# AST1041.net
KiCad netlist of a schematic drawn in EAGLE
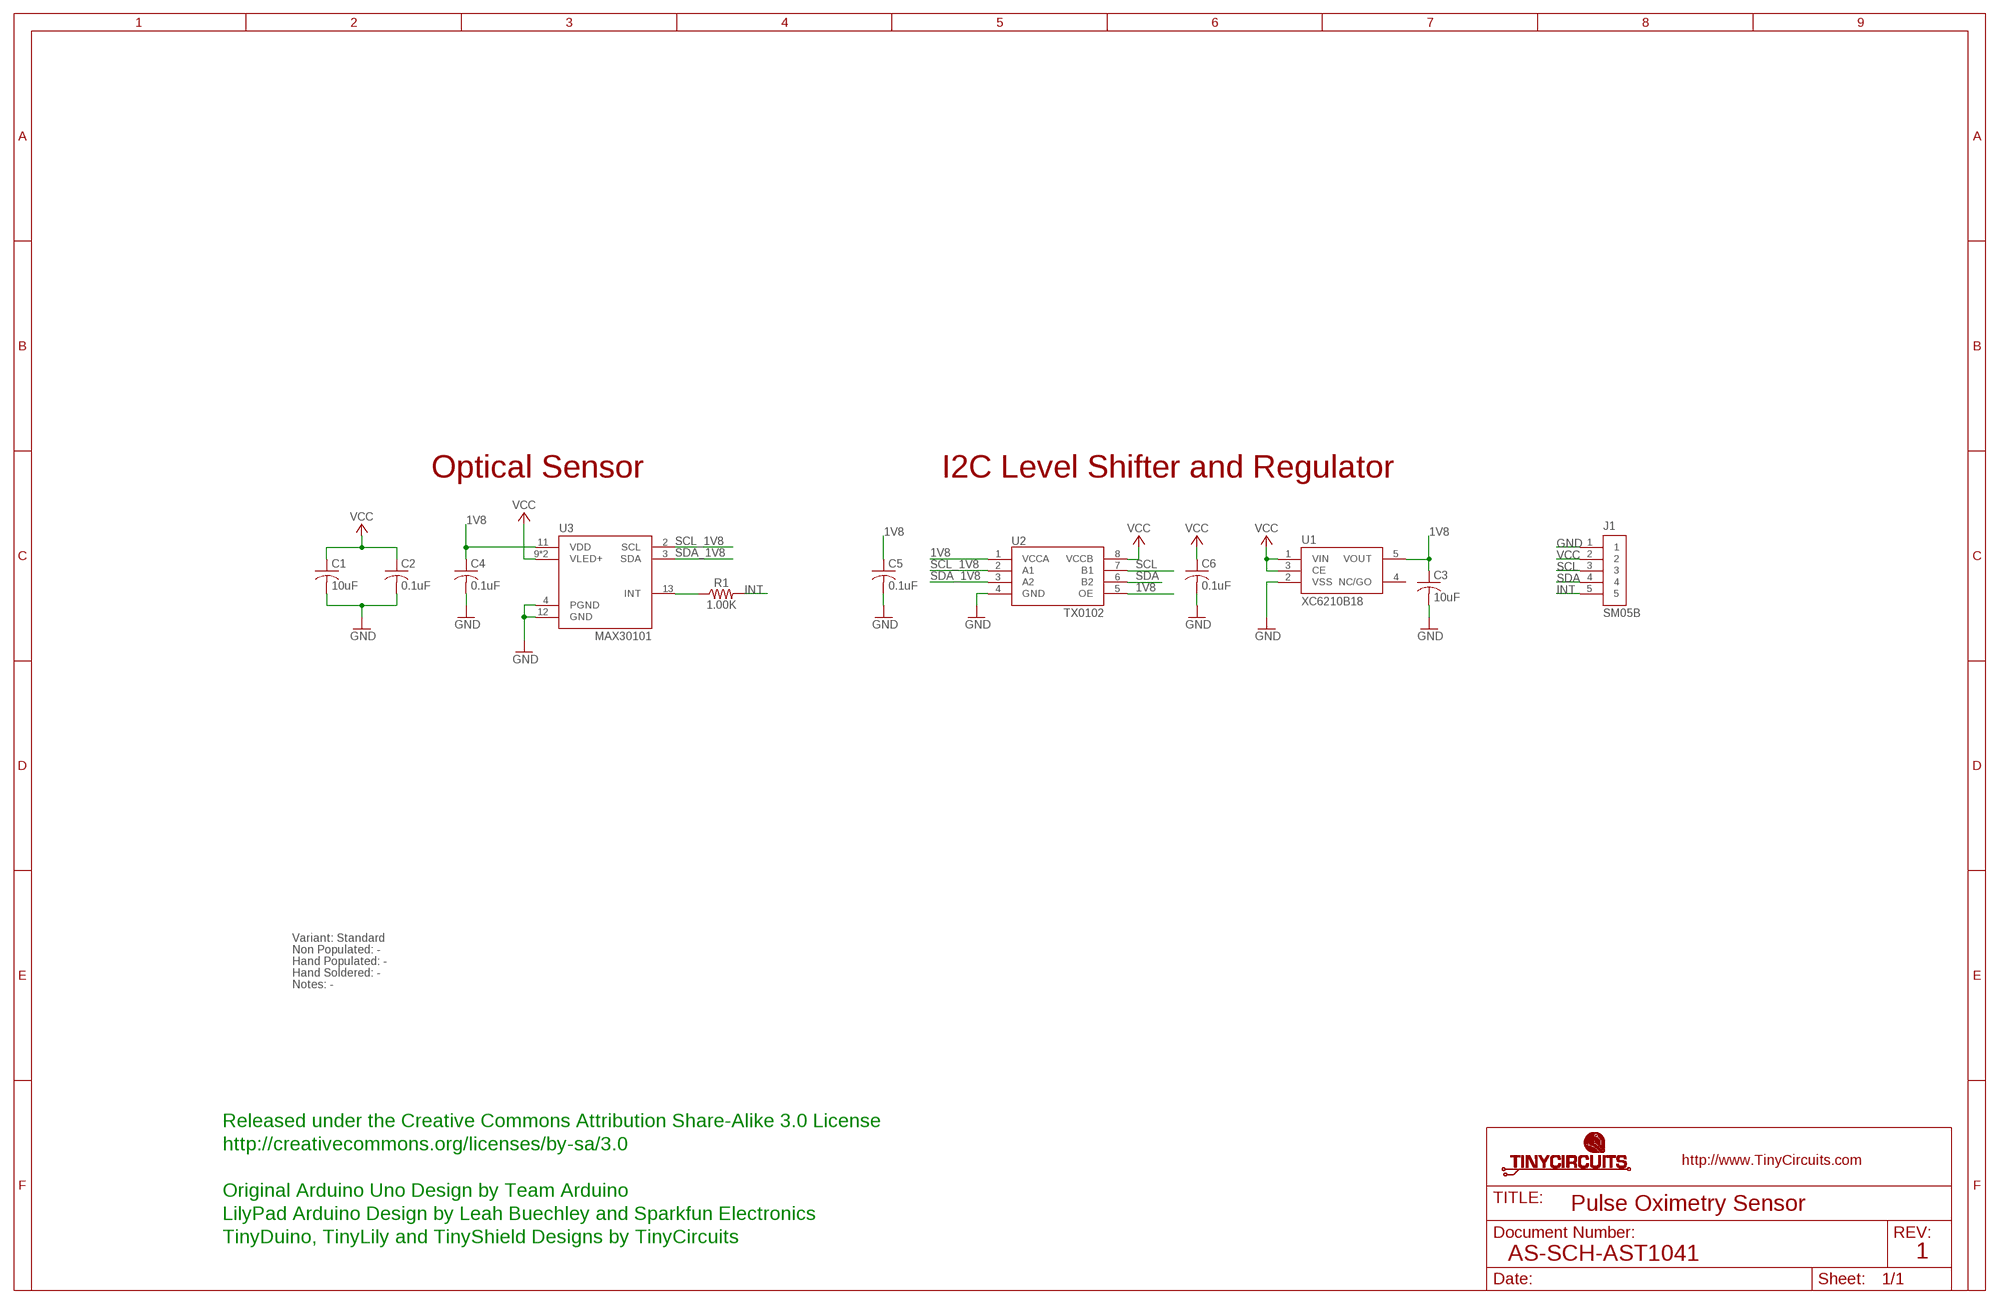
[diagram p0: schematic, sheet 1]

(export (version "E")
  (design (tool "Eeschema 10.0.6"))
  (components
    (comp (ref "C1")
      (value "10uF")
      (footprint "eagle-import:C0603")
      (fields (field (name "PARTNO") "AS-ITM-00002") (field (name "PARTNO_1") "AS-ITM-00002"))
      (libsource (lib "eagle-import") (part "AS-ITM-00002"))
    )
    (comp (ref "C2")
      (value "0.1uF")
      (footprint "eagle-import:C0402")
      (fields (field (name "PARTNO") "AS-ITM-00008"))
      (libsource (lib "eagle-import") (part "AS-ITM-00008"))
    )
    (comp (ref "C3")
      (value "10uF")
      (footprint "eagle-import:C0603")
      (fields (field (name "PARTNO") "AS-ITM-00002") (field (name "PARTNO_1") "AS-ITM-00002"))
      (libsource (lib "eagle-import") (part "AS-ITM-00002"))
    )
    (comp (ref "C4")
      (value "0.1uF")
      (footprint "eagle-import:C0402")
      (fields (field (name "PARTNO") "AS-ITM-00008") (field (name "PARTNO_1") "AS-ITM-00008"))
      (libsource (lib "eagle-import") (part "AS-ITM-00008"))
    )
    (comp (ref "C5")
      (value "0.1uF")
      (footprint "eagle-import:C0402")
      (fields (field (name "PARTNO") "AS-ITM-00008") (field (name "PARTNO_1") "AS-ITM-00008"))
      (libsource (lib "eagle-import") (part "AS-ITM-00008"))
    )
    (comp (ref "C6")
      (value "0.1uF")
      (footprint "eagle-import:C0402")
      (fields (field (name "PARTNO") "AS-ITM-00008") (field (name "PARTNO_1") "AS-ITM-00008"))
      (libsource (lib "eagle-import") (part "AS-ITM-00008"))
    )
    (comp (ref "J1")
      (value "SM05B")
      (footprint "eagle-import:JST_SH_5X1")
      (fields (field (name "PARTNO") "AS-ITM-00340"))
      (libsource (lib "eagle-import") (part "AS-ITM-00340"))
    )
    (comp (ref "R1")
      (value "1.00K")
      (footprint "eagle-import:0402")
      (fields (field (name "PARTNO") "AS-ITM-00003"))
      (libsource (lib "eagle-import") (part "AS-ITM-00003"))
    )
    (comp (ref "U1")
      (value "XC6210B18")
      (footprint "eagle-import:SOT-25@1")
      (fields (field (name "PARTNO") "AS-ITM-00075"))
      (libsource (lib "eagle-import") (part "AS-ITM-00075"))
    )
    (comp (ref "U2")
      (value "TX0102")
      (footprint "eagle-import:DQE(R-PX2SON-N8)")
      (fields (field (name "PARTNO") "AS-ITM-00073"))
      (libsource (lib "eagle-import") (part "AS-ITM-00073"))
    )
    (comp (ref "U3")
      (value "MAX30101")
      (footprint "eagle-import:MAX30100")
      (fields (field (name "PARTNO") "AS-ITM-00473"))
      (libsource (lib "eagle-import") (part "AS-ITM-00473"))
    )
  )
  (nets
    (net (code "1") (name "/1V8") (class "Default")
      (node (ref "C3") (pin "1") (pinfunction "1_1") (pintype "passive"))
      (node (ref "C4") (pin "1") (pinfunction "1_1") (pintype "passive"))
      (node (ref "C5") (pin "1") (pinfunction "1_1") (pintype "passive"))
      (node (ref "U1") (pin "5") (pinfunction "VOUT_5") (pintype "bidirectional"))
      (node (ref "U2") (pin "1") (pinfunction "VCCA_1") (pintype "bidirectional"))
      (node (ref "U2") (pin "5") (pinfunction "OE_5") (pintype "bidirectional"))
      (node (ref "U3") (pin "11") (pinfunction "VDD_11") (pintype "bidirectional"))
    )
    (net (code "2") (name "/INT") (class "Default")
      (node (ref "J1") (pin "5") (pinfunction "5_5") (pintype "bidirectional"))
      (node (ref "R1") (pin "2") (pinfunction "2_2") (pintype "passive"))
    )
    (net (code "3") (name "/SCL") (class "Default")
      (node (ref "J1") (pin "3") (pinfunction "3_3") (pintype "bidirectional"))
      (node (ref "U2") (pin "7") (pinfunction "B1_7") (pintype "bidirectional"))
    )
    (net (code "4") (name "/SCL_1V8") (class "Default")
      (node (ref "U2") (pin "2") (pinfunction "A1_2") (pintype "bidirectional"))
      (node (ref "U3") (pin "2") (pinfunction "SCL_2") (pintype "bidirectional"))
    )
    (net (code "5") (name "/SDA") (class "Default")
      (node (ref "J1") (pin "4") (pinfunction "4_4") (pintype "bidirectional"))
      (node (ref "U2") (pin "6") (pinfunction "B2_6") (pintype "bidirectional"))
    )
    (net (code "6") (name "/SDA_1V8") (class "Default")
      (node (ref "U2") (pin "3") (pinfunction "A2_3") (pintype "bidirectional"))
      (node (ref "U3") (pin "3") (pinfunction "SDA_3") (pintype "bidirectional"))
    )
    (net (code "7") (name "GND") (class "Default")
      (node (ref "C1") (pin "2") (pinfunction "2_2") (pintype "passive"))
      (node (ref "C2") (pin "2") (pinfunction "2_2") (pintype "passive"))
      (node (ref "C3") (pin "2") (pinfunction "2_2") (pintype "passive"))
      (node (ref "C4") (pin "2") (pinfunction "2_2") (pintype "passive"))
      (node (ref "C5") (pin "2") (pinfunction "2_2") (pintype "passive"))
      (node (ref "C6") (pin "2") (pinfunction "2_2") (pintype "passive"))
      (node (ref "J1") (pin "1") (pinfunction "1_1") (pintype "bidirectional"))
      (node (ref "U1") (pin "2") (pinfunction "VSS_2") (pintype "power_in"))
      (node (ref "U2") (pin "4") (pinfunction "GND_4") (pintype "bidirectional"))
      (node (ref "U3") (pin "12") (pinfunction "GND_12") (pintype "bidirectional"))
      (node (ref "U3") (pin "4") (pinfunction "PGND_4") (pintype "bidirectional"))
    )
    (net (code "8") (name "Net-(U3-INT)") (class "Default")
      (node (ref "R1") (pin "1") (pinfunction "1_1") (pintype "passive"))
      (node (ref "U3") (pin "13") (pinfunction "INT_13") (pintype "bidirectional"))
    )
    (net (code "9") (name "VCC") (class "Default")
      (node (ref "C1") (pin "1") (pinfunction "1_1") (pintype "passive"))
      (node (ref "C2") (pin "1") (pinfunction "1_1") (pintype "passive"))
      (node (ref "C6") (pin "1") (pinfunction "1_1") (pintype "passive"))
      (node (ref "J1") (pin "2") (pinfunction "2_2") (pintype "bidirectional"))
      (node (ref "U1") (pin "1") (pinfunction "VIN_1") (pintype "bidirectional"))
      (node (ref "U1") (pin "3") (pinfunction "CE_3") (pintype "bidirectional"))
      (node (ref "U2") (pin "8") (pinfunction "VCCB_8") (pintype "bidirectional"))
      (node (ref "U3") (pin "10") (pinfunction "VLED+_10") (pintype "bidirectional"))
      (node (ref "U3") (pin "9") (pinfunction "VLED+_9") (pintype "bidirectional"))
    )
    (net (code "10") (name "unconnected-(U1-NC{slash}GO-Pad4)") (class "Default")
      (node (ref "U1") (pin "4") (pinfunction "NC/GO_4") (pintype "bidirectional"))
    )
  )
)
